# mainboard.net
KiCad netlist of a schematic drawn in EAGLE
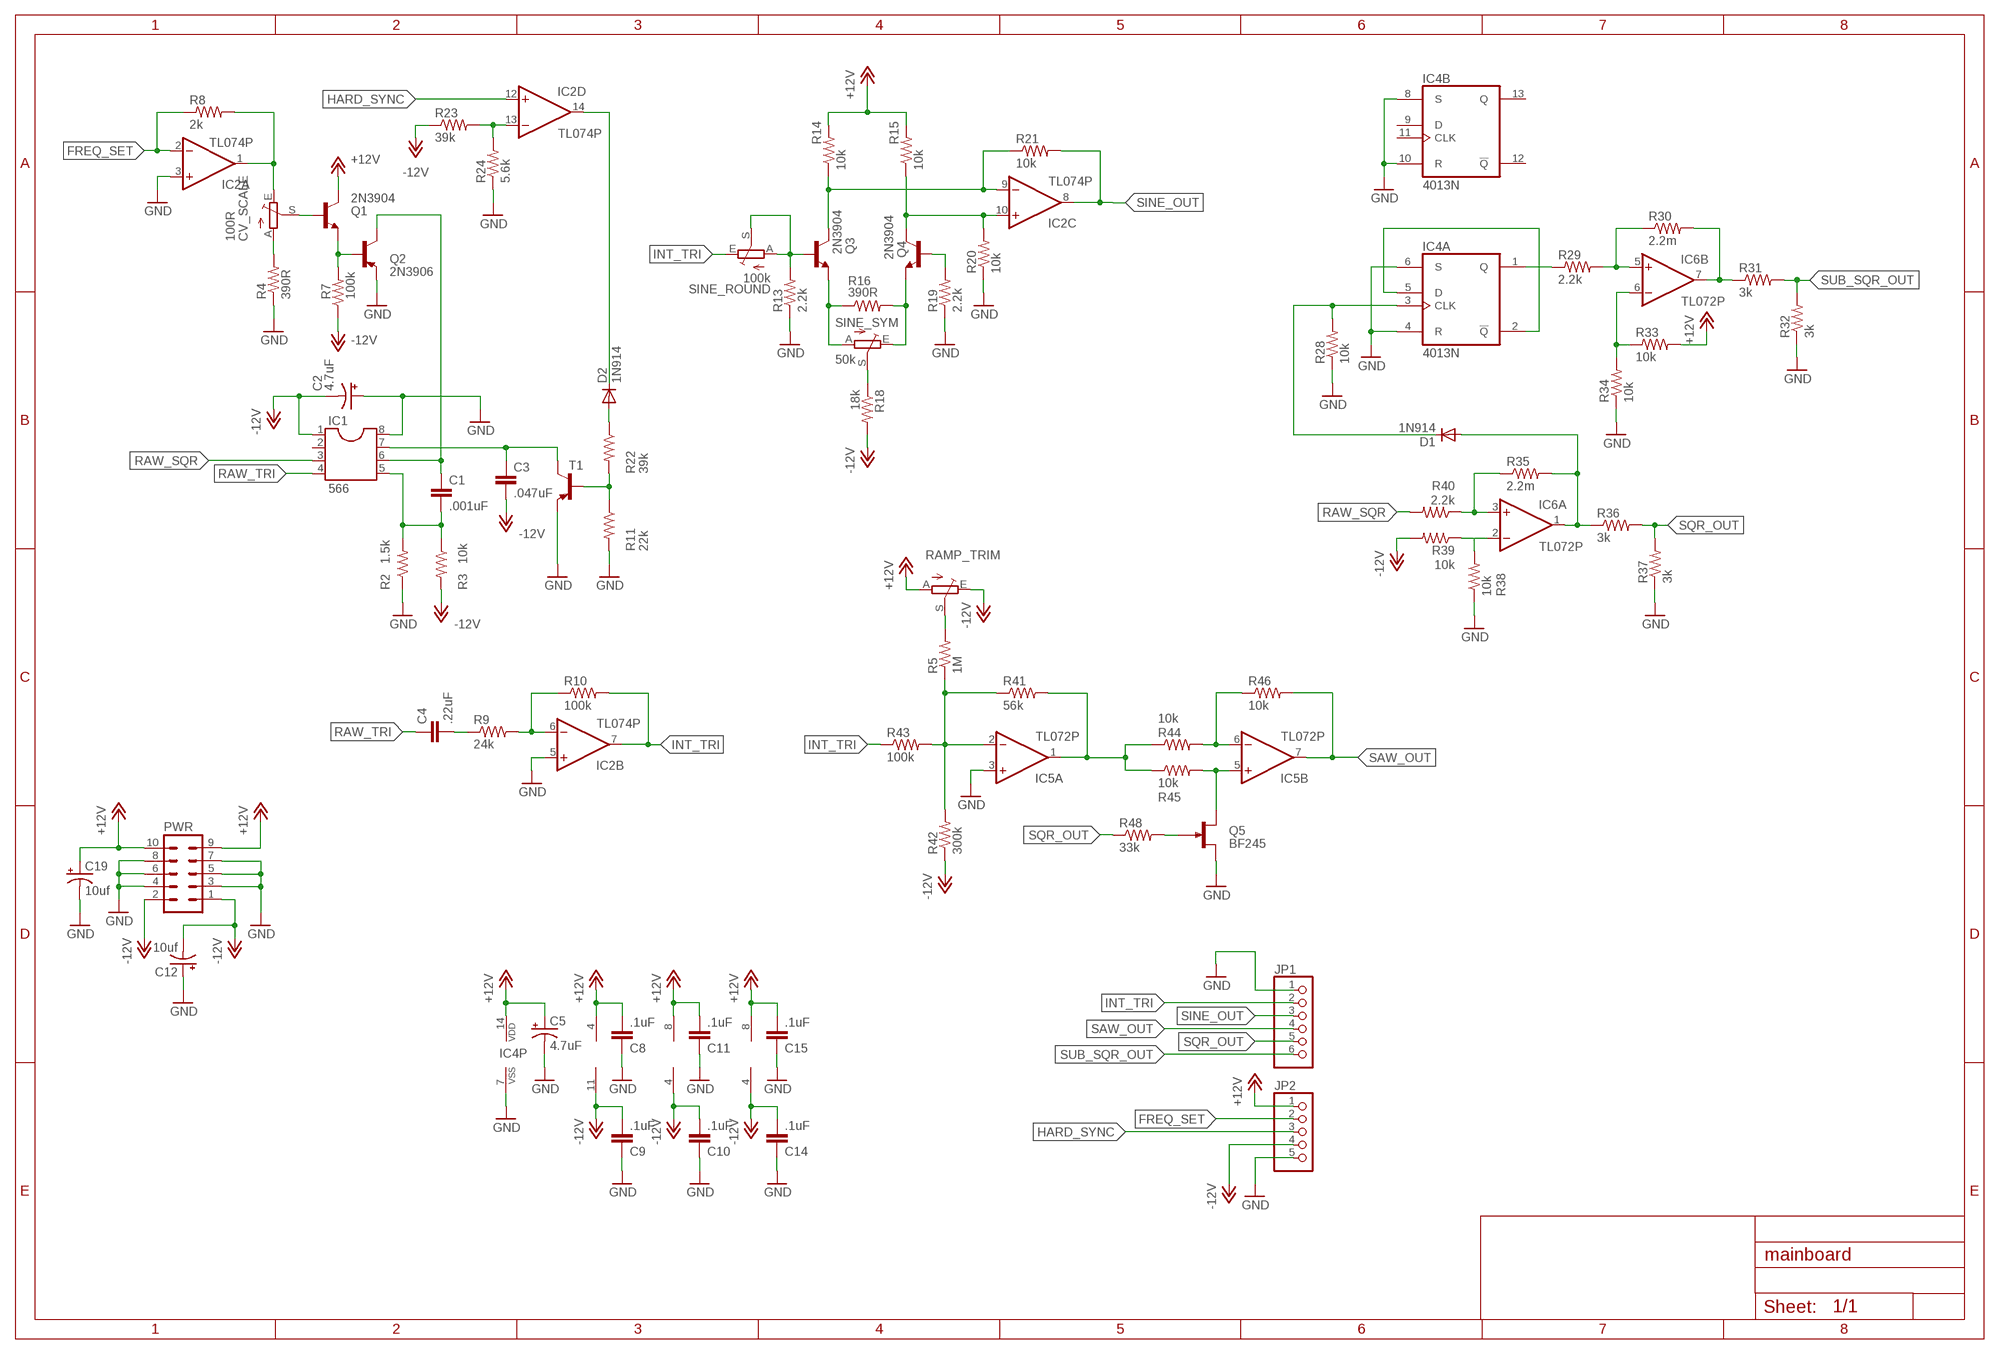
[diagram p0: schematic, sheet 1]

(export (version "E")
  (design (tool "Eeschema 10.0.6"))
  (components
    (comp (ref "C1")
      (value ".001uF")
      (footprint "eagle-import:C050-024X044")
      (libsource (lib "eagle-import") (part "C-EU050-024X044"))
    )
    (comp (ref "C2")
      (value "4.7uF")
      (footprint "eagle-import:E2,5-6")
      (libsource (lib "eagle-import") (part "CPOL-USE2.5-6"))
    )
    (comp (ref "C3")
      (value ".047uF")
      (footprint "eagle-import:C050-024X044")
      (libsource (lib "eagle-import") (part "C-EU050-024X044"))
    )
    (comp (ref "C4")
      (value ".22uF")
      (footprint "eagle-import:C050-024X044")
      (libsource (lib "eagle-import") (part "C-EU050-024X044"))
    )
    (comp (ref "C5")
      (value "4.7uF")
      (footprint "eagle-import:E2,5-5")
      (libsource (lib "eagle-import") (part "CPOL-USE2.5-5"))
    )
    (comp (ref "C8")
      (value ".1uF")
      (footprint "eagle-import:C050-024X044")
      (libsource (lib "eagle-import") (part "C-EU050-024X044"))
    )
    (comp (ref "C9")
      (value ".1uF")
      (footprint "eagle-import:C050-024X044")
      (libsource (lib "eagle-import") (part "C-EU050-024X044"))
    )
    (comp (ref "C10")
      (value ".1uF")
      (footprint "eagle-import:C050-024X044")
      (libsource (lib "eagle-import") (part "C-EU050-024X044"))
    )
    (comp (ref "C11")
      (value ".1uF")
      (footprint "eagle-import:C050-024X044")
      (libsource (lib "eagle-import") (part "C-EU050-024X044"))
    )
    (comp (ref "C12")
      (value "10uf")
      (footprint "eagle-import:E2,5-5")
      (libsource (lib "eagle-import") (part "CPOL-USE2.5-5"))
    )
    (comp (ref "C14")
      (value ".1uF")
      (footprint "eagle-import:C050-024X044")
      (libsource (lib "eagle-import") (part "C-EU050-024X044"))
    )
    (comp (ref "C15")
      (value ".1uF")
      (footprint "eagle-import:C050-024X044")
      (libsource (lib "eagle-import") (part "C-EU050-024X044"))
    )
    (comp (ref "C19")
      (value "10uf")
      (footprint "eagle-import:E2,5-5")
      (libsource (lib "eagle-import") (part "CPOL-USE2.5-5"))
    )
    (comp (ref "CV_SCALE")
      (value "100R")
      (footprint "eagle-import:RJ9W")
      (libsource (lib "eagle-import") (part "TRIM_EU-RJ9W"))
    )
    (comp (ref "D1")
      (value "1N914")
      (footprint "eagle-import:DO35-7")
      (libsource (lib "eagle-import") (part "1N4148DO35-7"))
    )
    (comp (ref "D2")
      (value "1N914")
      (footprint "eagle-import:DO35-7")
      (libsource (lib "eagle-import") (part "1N4148DO35-7"))
    )
    (comp (ref "IC1")
      (value "566")
      (footprint "eagle-import:DIL08")
      (libsource (lib "eagle-import") (part "DIL8"))
    )
    (comp (ref "IC2")
      (value "TL074P")
      (footprint "eagle-import:DIL14")
      (libsource (lib "eagle-import") (part "TL074P"))
    )
    (comp (ref "IC4")
      (value "4013N")
      (footprint "eagle-import:DIL14")
      (libsource (lib "eagle-import") (part "4013N"))
    )
    (comp (ref "IC5")
      (value "TL072P")
      (footprint "eagle-import:DIL08")
      (libsource (lib "eagle-import") (part "TL072P"))
    )
    (comp (ref "IC6")
      (value "TL072P")
      (footprint "eagle-import:DIL08")
      (libsource (lib "eagle-import") (part "TL072P"))
    )
    (comp (ref "JP1")
      (value "PINHD-1X6")
      (footprint "eagle-import:1X06")
      (libsource (lib "eagle-import") (part "PINHD-1X6"))
    )
    (comp (ref "JP2")
      (value "PINHD-1X5")
      (footprint "eagle-import:1X05")
      (libsource (lib "eagle-import") (part "PINHD-1X5"))
    )
    (comp (ref "PWR")
      (value "ML10")
      (footprint "eagle-import:ML10")
      (libsource (lib "eagle-import") (part "ML10"))
    )
    (comp (ref "Q1")
      (value "2N3904")
      (footprint "eagle-import:TO92")
      (libsource (lib "eagle-import") (part "2N3904"))
    )
    (comp (ref "Q2")
      (value "2N3906")
      (footprint "eagle-import:TO92")
      (libsource (lib "eagle-import") (part "2N3906"))
    )
    (comp (ref "Q3")
      (value "2N3904")
      (footprint "eagle-import:TO92")
      (libsource (lib "eagle-import") (part "2N3904"))
    )
    (comp (ref "Q4")
      (value "2N3904")
      (footprint "eagle-import:TO92")
      (libsource (lib "eagle-import") (part "2N3904"))
    )
    (comp (ref "Q5")
      (value "BF245")
      (footprint "eagle-import:SOT54C")
      (libsource (lib "eagle-import") (part "BF245"))
    )
    (comp (ref "R2")
      (value "1.5k")
      (footprint "eagle-import:0204_7")
      (libsource (lib "eagle-import") (part "R-US_0204/7"))
    )
    (comp (ref "R3")
      (value "10k")
      (footprint "eagle-import:0204_7")
      (libsource (lib "eagle-import") (part "R-US_0204/7"))
    )
    (comp (ref "R4")
      (value "390R")
      (footprint "eagle-import:0204_7")
      (libsource (lib "eagle-import") (part "R-US_0204/7"))
    )
    (comp (ref "R5")
      (value "1M")
      (footprint "eagle-import:0204_7")
      (libsource (lib "eagle-import") (part "R-US_0204/7"))
    )
    (comp (ref "R7")
      (value "100k")
      (footprint "eagle-import:0204_7")
      (libsource (lib "eagle-import") (part "R-US_0204/7"))
    )
    (comp (ref "R8")
      (value "2k")
      (footprint "eagle-import:0204_7")
      (libsource (lib "eagle-import") (part "R-US_0204/7"))
    )
    (comp (ref "R9")
      (value "24k")
      (footprint "eagle-import:0204_7")
      (libsource (lib "eagle-import") (part "R-US_0204/7"))
    )
    (comp (ref "R10")
      (value "100k")
      (footprint "eagle-import:0204_7")
      (libsource (lib "eagle-import") (part "R-US_0204/7"))
    )
    (comp (ref "R11")
      (value "22k")
      (footprint "eagle-import:0204_7")
      (libsource (lib "eagle-import") (part "R-US_0204/7"))
    )
    (comp (ref "R13")
      (value "2.2k")
      (footprint "eagle-import:0204_7")
      (libsource (lib "eagle-import") (part "R-US_0204/7"))
    )
    (comp (ref "R14")
      (value "10k")
      (footprint "eagle-import:0204_7")
      (libsource (lib "eagle-import") (part "R-US_0204/7"))
    )
    (comp (ref "R15")
      (value "10k")
      (footprint "eagle-import:0204_7")
      (libsource (lib "eagle-import") (part "R-US_0204/7"))
    )
    (comp (ref "R16")
      (value "390R")
      (footprint "eagle-import:0204_7")
      (libsource (lib "eagle-import") (part "R-US_0204/7"))
    )
    (comp (ref "R18")
      (value "18k")
      (footprint "eagle-import:0204_7")
      (libsource (lib "eagle-import") (part "R-US_0204/7"))
    )
    (comp (ref "R19")
      (value "2.2k")
      (footprint "eagle-import:0204_7")
      (libsource (lib "eagle-import") (part "R-US_0204/7"))
    )
    (comp (ref "R20")
      (value "10k")
      (footprint "eagle-import:0204_7")
      (libsource (lib "eagle-import") (part "R-US_0204/7"))
    )
    (comp (ref "R21")
      (value "10k")
      (footprint "eagle-import:0204_7")
      (libsource (lib "eagle-import") (part "R-US_0204/7"))
    )
    (comp (ref "R22")
      (value "39k")
      (footprint "eagle-import:0204_7")
      (libsource (lib "eagle-import") (part "R-US_0204/7"))
    )
    (comp (ref "R23")
      (value "39k")
      (footprint "eagle-import:0204_7")
      (libsource (lib "eagle-import") (part "R-US_0204/7"))
    )
    (comp (ref "R24")
      (value "5.6k")
      (footprint "eagle-import:0204_7")
      (libsource (lib "eagle-import") (part "R-US_0204/7"))
    )
    (comp (ref "R28")
      (value "10k")
      (footprint "eagle-import:0204_7")
      (libsource (lib "eagle-import") (part "R-US_0204/7"))
    )
    (comp (ref "R29")
      (value "2.2k")
      (footprint "eagle-import:0204_7")
      (libsource (lib "eagle-import") (part "R-US_0204/7"))
    )
    (comp (ref "R30")
      (value "2.2m")
      (footprint "eagle-import:0204_7")
      (libsource (lib "eagle-import") (part "R-US_0204/7"))
    )
    (comp (ref "R31")
      (value "3k")
      (footprint "eagle-import:0204_7")
      (libsource (lib "eagle-import") (part "R-US_0204/7"))
    )
    (comp (ref "R32")
      (value "3k")
      (footprint "eagle-import:0204_7")
      (libsource (lib "eagle-import") (part "R-US_0204/7"))
    )
    (comp (ref "R33")
      (value "10k")
      (footprint "eagle-import:0204_7")
      (libsource (lib "eagle-import") (part "R-US_0204/7"))
    )
    (comp (ref "R34")
      (value "10k")
      (footprint "eagle-import:0204_7")
      (libsource (lib "eagle-import") (part "R-US_0204/7"))
    )
    (comp (ref "R35")
      (value "2.2m")
      (footprint "eagle-import:0204_7")
      (libsource (lib "eagle-import") (part "R-US_0204/7"))
    )
    (comp (ref "R36")
      (value "3k")
      (footprint "eagle-import:0204_7")
      (libsource (lib "eagle-import") (part "R-US_0204/7"))
    )
    (comp (ref "R37")
      (value "3k")
      (footprint "eagle-import:0204_7")
      (libsource (lib "eagle-import") (part "R-US_0204/7"))
    )
    (comp (ref "R38")
      (value "10k")
      (footprint "eagle-import:0204_7")
      (libsource (lib "eagle-import") (part "R-US_0204/7"))
    )
    (comp (ref "R39")
      (value "10k")
      (footprint "eagle-import:0204_7")
      (libsource (lib "eagle-import") (part "R-US_0204/7"))
    )
    (comp (ref "R40")
      (value "2.2k")
      (footprint "eagle-import:0204_7")
      (libsource (lib "eagle-import") (part "R-US_0204/7"))
    )
    (comp (ref "R41")
      (value "56k")
      (footprint "eagle-import:0204_7")
      (libsource (lib "eagle-import") (part "R-US_0204/7"))
    )
    (comp (ref "R42")
      (value "300k")
      (footprint "eagle-import:0204_7")
      (libsource (lib "eagle-import") (part "R-US_0204/7"))
    )
    (comp (ref "R43")
      (value "100k")
      (footprint "eagle-import:0204_7")
      (libsource (lib "eagle-import") (part "R-US_0204/7"))
    )
    (comp (ref "R44")
      (value "10k")
      (footprint "eagle-import:0204_7")
      (libsource (lib "eagle-import") (part "R-US_0204/7"))
    )
    (comp (ref "R45")
      (value "10k")
      (footprint "eagle-import:0204_7")
      (libsource (lib "eagle-import") (part "R-US_0204/7"))
    )
    (comp (ref "R46")
      (value "10k")
      (footprint "eagle-import:0204_7")
      (libsource (lib "eagle-import") (part "R-US_0204/7"))
    )
    (comp (ref "R48")
      (value "33k")
      (footprint "eagle-import:0204_7")
      (libsource (lib "eagle-import") (part "R-US_0204/7"))
    )
    (comp (ref "RAMP_TRIM")
      (value "TRIM_EU-RJ9W")
      (footprint "eagle-import:RJ9W")
      (libsource (lib "eagle-import") (part "TRIM_EU-RJ9W"))
    )
    (comp (ref "SINE_ROUND")
      (value "100k")
      (footprint "eagle-import:RJ9W")
      (libsource (lib "eagle-import") (part "TRIM_EU-RJ9W"))
    )
    (comp (ref "SINE_SYM")
      (value "50k")
      (footprint "eagle-import:RJ9W")
      (libsource (lib "eagle-import") (part "TRIM_EU-RJ9W"))
    )
    (comp (ref "T1")
      (value "2N3906-PNP-TO92-EBC")
      (footprint "eagle-import:TO92-EBC")
      (libsource (lib "eagle-import") (part "-PNP-TO92-EBC2N3906"))
    )
  )
  (nets
    (net (code "1") (name "+12V") (class "Default")
      (node (ref "C11") (pin "2") (pinfunction "2_2") (pintype "passive"))
      (node (ref "C15") (pin "2") (pinfunction "2_2") (pintype "passive"))
      (node (ref "C19") (pin "+") (pinfunction "+_+") (pintype "passive"))
      (node (ref "C5") (pin "+") (pinfunction "+_+") (pintype "passive"))
      (node (ref "C8") (pin "2") (pinfunction "2_2") (pintype "passive"))
      (node (ref "IC2") (pin "4") (pinfunction "V+_4") (pintype "power_in"))
      (node (ref "IC4") (pin "14") (pinfunction "VDD_14") (pintype "power_in"))
      (node (ref "IC5") (pin "8") (pinfunction "V+_8") (pintype "power_in"))
      (node (ref "IC6") (pin "8") (pinfunction "V+_8") (pintype "power_in"))
      (node (ref "JP2") (pin "1") (pinfunction "1_1") (pintype "passive"))
      (node (ref "PWR") (pin "10") (pinfunction "10_10") (pintype "passive"))
      (node (ref "PWR") (pin "9") (pinfunction "9_9") (pintype "passive"))
      (node (ref "Q1") (pin "1") (pinfunction "C_1") (pintype "passive"))
      (node (ref "R14") (pin "2") (pinfunction "2_2") (pintype "passive"))
      (node (ref "R15") (pin "2") (pinfunction "2_2") (pintype "passive"))
      (node (ref "R33") (pin "2") (pinfunction "2_2") (pintype "passive"))
      (node (ref "RAMP_TRIM") (pin "A") (pinfunction "A_A") (pintype "passive"))
    )
    (net (code "2") (name "-12V") (class "Default")
      (node (ref "C10") (pin "2") (pinfunction "2_2") (pintype "passive"))
      (node (ref "C12") (pin "-") (pinfunction "-_-") (pintype "passive"))
      (node (ref "C14") (pin "2") (pinfunction "2_2") (pintype "passive"))
      (node (ref "C2") (pin "-") (pinfunction "-_-") (pintype "passive"))
      (node (ref "C3") (pin "2") (pinfunction "2_2") (pintype "passive"))
      (node (ref "C9") (pin "2") (pinfunction "2_2") (pintype "passive"))
      (node (ref "IC1") (pin "1") (pinfunction "1_1") (pintype "passive"))
      (node (ref "IC2") (pin "11") (pinfunction "V-_11") (pintype "power_in"))
      (node (ref "IC5") (pin "4") (pinfunction "V-_4") (pintype "power_in"))
      (node (ref "IC6") (pin "4") (pinfunction "V-_4") (pintype "power_in"))
      (node (ref "JP2") (pin "4") (pinfunction "4_4") (pintype "passive"))
      (node (ref "PWR") (pin "1") (pinfunction "1_1") (pintype "passive"))
      (node (ref "PWR") (pin "2") (pinfunction "2_2") (pintype "passive"))
      (node (ref "R18") (pin "2") (pinfunction "2_2") (pintype "passive"))
      (node (ref "R23") (pin "1") (pinfunction "1_1") (pintype "passive"))
      (node (ref "R3") (pin "2") (pinfunction "2_2") (pintype "passive"))
      (node (ref "R39") (pin "2") (pinfunction "2_2") (pintype "passive"))
      (node (ref "R42") (pin "1") (pinfunction "1_1") (pintype "passive"))
      (node (ref "R7") (pin "1") (pinfunction "1_1") (pintype "passive"))
      (node (ref "RAMP_TRIM") (pin "E") (pinfunction "E_E") (pintype "passive"))
    )
    (net (code "3") (name "FREQ_SET") (class "Default")
      (node (ref "IC2") (pin "2") (pinfunction "-IN_2") (pintype "input"))
      (node (ref "JP2") (pin "2") (pinfunction "2_2") (pintype "passive"))
      (node (ref "R8") (pin "1") (pinfunction "1_1") (pintype "passive"))
    )
    (net (code "4") (name "GND") (class "Default")
      (node (ref "C10") (pin "1") (pinfunction "1_1") (pintype "passive"))
      (node (ref "C11") (pin "1") (pinfunction "1_1") (pintype "passive"))
      (node (ref "C12") (pin "+") (pinfunction "+_+") (pintype "passive"))
      (node (ref "C14") (pin "1") (pinfunction "1_1") (pintype "passive"))
      (node (ref "C15") (pin "1") (pinfunction "1_1") (pintype "passive"))
      (node (ref "C19") (pin "-") (pinfunction "-_-") (pintype "passive"))
      (node (ref "C2") (pin "+") (pinfunction "+_+") (pintype "passive"))
      (node (ref "C5") (pin "-") (pinfunction "-_-") (pintype "passive"))
      (node (ref "C8") (pin "1") (pinfunction "1_1") (pintype "passive"))
      (node (ref "C9") (pin "1") (pinfunction "1_1") (pintype "passive"))
      (node (ref "IC1") (pin "8") (pinfunction "8_8") (pintype "passive"))
      (node (ref "IC2") (pin "3") (pinfunction "+IN_3") (pintype "input"))
      (node (ref "IC2") (pin "5") (pinfunction "+IN_5") (pintype "input"))
      (node (ref "IC4") (pin "10") (pinfunction "R_10") (pintype "input"))
      (node (ref "IC4") (pin "4") (pinfunction "R_4") (pintype "input"))
      (node (ref "IC4") (pin "6") (pinfunction "S_6") (pintype "input"))
      (node (ref "IC4") (pin "7") (pinfunction "VSS_7") (pintype "power_in"))
      (node (ref "IC4") (pin "8") (pinfunction "S_8") (pintype "input"))
      (node (ref "IC5") (pin "3") (pinfunction "+IN_3") (pintype "input"))
      (node (ref "JP1") (pin "1") (pinfunction "1_1") (pintype "passive"))
      (node (ref "JP2") (pin "5") (pinfunction "5_5") (pintype "passive"))
      (node (ref "PWR") (pin "3") (pinfunction "3_3") (pintype "passive"))
      (node (ref "PWR") (pin "4") (pinfunction "4_4") (pintype "passive"))
      (node (ref "PWR") (pin "5") (pinfunction "5_5") (pintype "passive"))
      (node (ref "PWR") (pin "6") (pinfunction "6_6") (pintype "passive"))
      (node (ref "PWR") (pin "7") (pinfunction "7_7") (pintype "passive"))
      (node (ref "PWR") (pin "8") (pinfunction "8_8") (pintype "passive"))
      (node (ref "Q2") (pin "3") (pinfunction "E_3") (pintype "passive"))
      (node (ref "Q5") (pin "S") (pinfunction "S_S") (pintype "passive"))
      (node (ref "R11") (pin "2") (pinfunction "2_2") (pintype "passive"))
      (node (ref "R13") (pin "1") (pinfunction "1_1") (pintype "passive"))
      (node (ref "R19") (pin "1") (pinfunction "1_1") (pintype "passive"))
      (node (ref "R2") (pin "1") (pinfunction "1_1") (pintype "passive"))
      (node (ref "R20") (pin "1") (pinfunction "1_1") (pintype "passive"))
      (node (ref "R24") (pin "1") (pinfunction "1_1") (pintype "passive"))
      (node (ref "R28") (pin "1") (pinfunction "1_1") (pintype "passive"))
      (node (ref "R32") (pin "1") (pinfunction "1_1") (pintype "passive"))
      (node (ref "R34") (pin "1") (pinfunction "1_1") (pintype "passive"))
      (node (ref "R37") (pin "1") (pinfunction "1_1") (pintype "passive"))
      (node (ref "R38") (pin "1") (pinfunction "1_1") (pintype "passive"))
      (node (ref "R4") (pin "1") (pinfunction "1_1") (pintype "passive"))
      (node (ref "T1") (pin "E") (pinfunction "E_E") (pintype "passive"))
    )
    (net (code "5") (name "HARD_SYNC") (class "Default")
      (node (ref "IC2") (pin "12") (pinfunction "+IN_12") (pintype "input"))
      (node (ref "JP2") (pin "3") (pinfunction "3_3") (pintype "passive"))
    )
    (net (code "6") (name "INT_TRI") (class "Default")
      (node (ref "IC2") (pin "7") (pinfunction "OUT_7") (pintype "output"))
      (node (ref "JP1") (pin "2") (pinfunction "2_2") (pintype "passive"))
      (node (ref "R10") (pin "2") (pinfunction "2_2") (pintype "passive"))
      (node (ref "R43") (pin "1") (pinfunction "1_1") (pintype "passive"))
      (node (ref "SINE_ROUND") (pin "E") (pinfunction "E_E") (pintype "passive"))
    )
    (net (code "7") (name "Net-(C1-Pad2)") (class "Default")
      (node (ref "C1") (pin "2") (pinfunction "2_2") (pintype "passive"))
      (node (ref "IC1") (pin "5") (pinfunction "5_5") (pintype "passive"))
      (node (ref "R2") (pin "2") (pinfunction "2_2") (pintype "passive"))
      (node (ref "R3") (pin "1") (pinfunction "1_1") (pintype "passive"))
    )
    (net (code "8") (name "Net-(C3-Pad1)") (class "Default")
      (node (ref "C3") (pin "1") (pinfunction "1_1") (pintype "passive"))
      (node (ref "IC1") (pin "7") (pinfunction "7_7") (pintype "passive"))
      (node (ref "T1") (pin "C") (pinfunction "C_C") (pintype "passive"))
    )
    (net (code "9") (name "Net-(C4-Pad2)") (class "Default")
      (node (ref "C4") (pin "2") (pinfunction "2_2") (pintype "passive"))
      (node (ref "R9") (pin "1") (pinfunction "1_1") (pintype "passive"))
    )
    (net (code "10") (name "Net-(CV_SCALE-PadA)") (class "Default")
      (node (ref "CV_SCALE") (pin "A") (pinfunction "A_A") (pintype "passive"))
      (node (ref "R4") (pin "2") (pinfunction "2_2") (pintype "passive"))
    )
    (net (code "11") (name "Net-(D2-PadA)") (class "Default")
      (node (ref "D2") (pin "A") (pinfunction "A_A") (pintype "passive"))
      (node (ref "R22") (pin "1") (pinfunction "1_1") (pintype "passive"))
    )
    (net (code "12") (name "Net-(IC2A-OUT)") (class "Default")
      (node (ref "CV_SCALE") (pin "E") (pinfunction "E_E") (pintype "passive"))
      (node (ref "IC2") (pin "1") (pinfunction "OUT_1") (pintype "output"))
      (node (ref "R8") (pin "2") (pinfunction "2_2") (pintype "passive"))
    )
    (net (code "13") (name "Net-(IC2B--IN)") (class "Default")
      (node (ref "IC2") (pin "6") (pinfunction "-IN_6") (pintype "input"))
      (node (ref "R10") (pin "1") (pinfunction "1_1") (pintype "passive"))
      (node (ref "R9") (pin "2") (pinfunction "2_2") (pintype "passive"))
    )
    (net (code "14") (name "Net-(IC2C-+IN)") (class "Default")
      (node (ref "IC2") (pin "10") (pinfunction "+IN_10") (pintype "input"))
      (node (ref "Q4") (pin "1") (pinfunction "C_1") (pintype "passive"))
      (node (ref "R15") (pin "1") (pinfunction "1_1") (pintype "passive"))
      (node (ref "R20") (pin "2") (pinfunction "2_2") (pintype "passive"))
    )
    (net (code "15") (name "Net-(IC2C--IN)") (class "Default")
      (node (ref "IC2") (pin "9") (pinfunction "-IN_9") (pintype "input"))
      (node (ref "Q3") (pin "1") (pinfunction "C_1") (pintype "passive"))
      (node (ref "R14") (pin "1") (pinfunction "1_1") (pintype "passive"))
      (node (ref "R21") (pin "1") (pinfunction "1_1") (pintype "passive"))
    )
    (net (code "16") (name "Net-(IC2D--IN)") (class "Default")
      (node (ref "IC2") (pin "13") (pinfunction "-IN_13") (pintype "input"))
      (node (ref "R23") (pin "2") (pinfunction "2_2") (pintype "passive"))
      (node (ref "R24") (pin "2") (pinfunction "2_2") (pintype "passive"))
    )
    (net (code "17") (name "Net-(IC2D-OUT)") (class "Default")
      (node (ref "D2") (pin "C") (pinfunction "C_C") (pintype "passive"))
      (node (ref "IC2") (pin "14") (pinfunction "OUT_14") (pintype "output"))
    )
    (net (code "18") (name "Net-(IC4A-CLK)") (class "Default")
      (node (ref "D1") (pin "C") (pinfunction "C_C") (pintype "passive"))
      (node (ref "IC4") (pin "3") (pinfunction "CLK_3") (pintype "input"))
      (node (ref "R28") (pin "2") (pinfunction "2_2") (pintype "passive"))
    )
    (net (code "19") (name "Net-(IC4A-D)") (class "Default")
      (node (ref "IC4") (pin "2") (pinfunction "~{Q}_2") (pintype "output"))
      (node (ref "IC4") (pin "5") (pinfunction "D_5") (pintype "input"))
    )
    (net (code "20") (name "Net-(IC4A-Q)") (class "Default")
      (node (ref "IC4") (pin "1") (pinfunction "Q_1") (pintype "output"))
      (node (ref "R29") (pin "1") (pinfunction "1_1") (pintype "passive"))
    )
    (net (code "21") (name "Net-(IC5A--IN)") (class "Default")
      (node (ref "IC5") (pin "2") (pinfunction "-IN_2") (pintype "input"))
      (node (ref "R41") (pin "1") (pinfunction "1_1") (pintype "passive"))
      (node (ref "R42") (pin "2") (pinfunction "2_2") (pintype "passive"))
      (node (ref "R43") (pin "2") (pinfunction "2_2") (pintype "passive"))
      (node (ref "R5") (pin "1") (pinfunction "1_1") (pintype "passive"))
    )
    (net (code "22") (name "Net-(IC5A-OUT)") (class "Default")
      (node (ref "IC5") (pin "1") (pinfunction "OUT_1") (pintype "output"))
      (node (ref "R41") (pin "2") (pinfunction "2_2") (pintype "passive"))
      (node (ref "R44") (pin "1") (pinfunction "1_1") (pintype "passive"))
      (node (ref "R45") (pin "1") (pinfunction "1_1") (pintype "passive"))
    )
    (net (code "23") (name "Net-(IC5B-+IN)") (class "Default")
      (node (ref "IC5") (pin "5") (pinfunction "+IN_5") (pintype "input"))
      (node (ref "Q5") (pin "D") (pinfunction "D_D") (pintype "passive"))
      (node (ref "R45") (pin "2") (pinfunction "2_2") (pintype "passive"))
    )
    (net (code "24") (name "Net-(IC5B--IN)") (class "Default")
      (node (ref "IC5") (pin "6") (pinfunction "-IN_6") (pintype "input"))
      (node (ref "R44") (pin "2") (pinfunction "2_2") (pintype "passive"))
      (node (ref "R46") (pin "1") (pinfunction "1_1") (pintype "passive"))
    )
    (net (code "25") (name "Net-(IC6A-+IN)") (class "Default")
      (node (ref "IC6") (pin "3") (pinfunction "+IN_3") (pintype "input"))
      (node (ref "R35") (pin "1") (pinfunction "1_1") (pintype "passive"))
      (node (ref "R40") (pin "1") (pinfunction "1_1") (pintype "passive"))
    )
    (net (code "26") (name "Net-(IC6A--IN)") (class "Default")
      (node (ref "IC6") (pin "2") (pinfunction "-IN_2") (pintype "input"))
      (node (ref "R38") (pin "2") (pinfunction "2_2") (pintype "passive"))
      (node (ref "R39") (pin "1") (pinfunction "1_1") (pintype "passive"))
    )
    (net (code "27") (name "Net-(IC6A-OUT)") (class "Default")
      (node (ref "D1") (pin "A") (pinfunction "A_A") (pintype "passive"))
      (node (ref "IC6") (pin "1") (pinfunction "OUT_1") (pintype "output"))
      (node (ref "R35") (pin "2") (pinfunction "2_2") (pintype "passive"))
      (node (ref "R36") (pin "1") (pinfunction "1_1") (pintype "passive"))
    )
    (net (code "28") (name "Net-(IC6B-+IN)") (class "Default")
      (node (ref "IC6") (pin "5") (pinfunction "+IN_5") (pintype "input"))
      (node (ref "R29") (pin "2") (pinfunction "2_2") (pintype "passive"))
      (node (ref "R30") (pin "1") (pinfunction "1_1") (pintype "passive"))
    )
    (net (code "29") (name "Net-(IC6B--IN)") (class "Default")
      (node (ref "IC6") (pin "6") (pinfunction "-IN_6") (pintype "input"))
      (node (ref "R33") (pin "1") (pinfunction "1_1") (pintype "passive"))
      (node (ref "R34") (pin "2") (pinfunction "2_2") (pintype "passive"))
    )
    (net (code "30") (name "Net-(IC6B-OUT)") (class "Default")
      (node (ref "IC6") (pin "7") (pinfunction "OUT_7") (pintype "output"))
      (node (ref "R30") (pin "2") (pinfunction "2_2") (pintype "passive"))
      (node (ref "R31") (pin "1") (pinfunction "1_1") (pintype "passive"))
    )
    (net (code "31") (name "Net-(Q1-B)") (class "Default")
      (node (ref "CV_SCALE") (pin "S") (pinfunction "S_S") (pintype "passive"))
      (node (ref "Q1") (pin "2") (pinfunction "B_2") (pintype "passive"))
    )
    (net (code "32") (name "Net-(Q1-E)") (class "Default")
      (node (ref "Q1") (pin "3") (pinfunction "E_3") (pintype "passive"))
      (node (ref "Q2") (pin "2") (pinfunction "B_2") (pintype "passive"))
      (node (ref "R7") (pin "2") (pinfunction "2_2") (pintype "passive"))
    )
    (net (code "33") (name "Net-(Q2-C)") (class "Default")
      (node (ref "C1") (pin "1") (pinfunction "1_1") (pintype "passive"))
      (node (ref "IC1") (pin "6") (pinfunction "6_6") (pintype "passive"))
      (node (ref "Q2") (pin "1") (pinfunction "C_1") (pintype "passive"))
    )
    (net (code "34") (name "Net-(Q3-B)") (class "Default")
      (node (ref "Q3") (pin "2") (pinfunction "B_2") (pintype "passive"))
      (node (ref "R13") (pin "2") (pinfunction "2_2") (pintype "passive"))
      (node (ref "SINE_ROUND") (pin "A") (pinfunction "A_A") (pintype "passive"))
      (node (ref "SINE_ROUND") (pin "S") (pinfunction "S_S") (pintype "passive"))
    )
    (net (code "35") (name "Net-(Q3-E)") (class "Default")
      (node (ref "Q3") (pin "3") (pinfunction "E_3") (pintype "passive"))
      (node (ref "R16") (pin "1") (pinfunction "1_1") (pintype "passive"))
      (node (ref "SINE_SYM") (pin "A") (pinfunction "A_A") (pintype "passive"))
    )
    (net (code "36") (name "Net-(Q4-B)") (class "Default")
      (node (ref "Q4") (pin "2") (pinfunction "B_2") (pintype "passive"))
      (node (ref "R19") (pin "2") (pinfunction "2_2") (pintype "passive"))
    )
    (net (code "37") (name "Net-(Q4-E)") (class "Default")
      (node (ref "Q4") (pin "3") (pinfunction "E_3") (pintype "passive"))
      (node (ref "R16") (pin "2") (pinfunction "2_2") (pintype "passive"))
      (node (ref "SINE_SYM") (pin "E") (pinfunction "E_E") (pintype "passive"))
    )
    (net (code "38") (name "Net-(Q5-PadG)") (class "Default")
      (node (ref "Q5") (pin "G") (pinfunction "G_G") (pintype "passive"))
      (node (ref "R48") (pin "2") (pinfunction "2_2") (pintype "passive"))
    )
    (net (code "39") (name "Net-(R5-Pad2)") (class "Default")
      (node (ref "R5") (pin "2") (pinfunction "2_2") (pintype "passive"))
      (node (ref "RAMP_TRIM") (pin "S") (pinfunction "S_S") (pintype "passive"))
    )
    (net (code "40") (name "Net-(R11-Pad1)") (class "Default")
      (node (ref "R11") (pin "1") (pinfunction "1_1") (pintype "passive"))
      (node (ref "R22") (pin "2") (pinfunction "2_2") (pintype "passive"))
      (node (ref "T1") (pin "B") (pinfunction "B_B") (pintype "passive"))
    )
    (net (code "41") (name "Net-(R18-Pad1)") (class "Default")
      (node (ref "R18") (pin "1") (pinfunction "1_1") (pintype "passive"))
      (node (ref "SINE_SYM") (pin "S") (pinfunction "S_S") (pintype "passive"))
    )
    (net (code "42") (name "RAW_SQR") (class "Default")
      (node (ref "IC1") (pin "3") (pinfunction "3_3") (pintype "passive"))
      (node (ref "R40") (pin "2") (pinfunction "2_2") (pintype "passive"))
    )
    (net (code "43") (name "RAW_TRI") (class "Default")
      (node (ref "C4") (pin "1") (pinfunction "1_1") (pintype "passive"))
      (node (ref "IC1") (pin "4") (pinfunction "4_4") (pintype "passive"))
    )
    (net (code "44") (name "SAW_OUT") (class "Default")
      (node (ref "IC5") (pin "7") (pinfunction "OUT_7") (pintype "output"))
      (node (ref "JP1") (pin "4") (pinfunction "4_4") (pintype "passive"))
      (node (ref "R46") (pin "2") (pinfunction "2_2") (pintype "passive"))
    )
    (net (code "45") (name "SINE_OUT") (class "Default")
      (node (ref "IC2") (pin "8") (pinfunction "OUT_8") (pintype "output"))
      (node (ref "JP1") (pin "3") (pinfunction "3_3") (pintype "passive"))
      (node (ref "R21") (pin "2") (pinfunction "2_2") (pintype "passive"))
    )
    (net (code "46") (name "SQR_OUT") (class "Default")
      (node (ref "JP1") (pin "5") (pinfunction "5_5") (pintype "passive"))
      (node (ref "R36") (pin "2") (pinfunction "2_2") (pintype "passive"))
      (node (ref "R37") (pin "2") (pinfunction "2_2") (pintype "passive"))
      (node (ref "R48") (pin "1") (pinfunction "1_1") (pintype "passive"))
    )
    (net (code "47") (name "SUB_SQR_OUT") (class "Default")
      (node (ref "JP1") (pin "6") (pinfunction "6_6") (pintype "passive"))
      (node (ref "R31") (pin "2") (pinfunction "2_2") (pintype "passive"))
      (node (ref "R32") (pin "2") (pinfunction "2_2") (pintype "passive"))
    )
    (net (code "48") (name "unconnected-(IC1-Pad2)") (class "Default")
      (node (ref "IC1") (pin "2") (pinfunction "2_2") (pintype "passive"))
    )
    (net (code "49") (name "unconnected-(IC4B-CLK-Pad11)") (class "Default")
      (node (ref "IC4") (pin "11") (pinfunction "CLK_11") (pintype "input"))
    )
    (net (code "50") (name "unconnected-(IC4B-D-Pad9)") (class "Default")
      (node (ref "IC4") (pin "9") (pinfunction "D_9") (pintype "input"))
    )
    (net (code "51") (name "unconnected-(IC4B-Q-Pad13)") (class "Default")
      (node (ref "IC4") (pin "13") (pinfunction "Q_13") (pintype "output"))
    )
    (net (code "52") (name "unconnected-(IC4B-~{Q}-Pad12)") (class "Default")
      (node (ref "IC4") (pin "12") (pinfunction "~{Q}_12") (pintype "output"))
    )
  )
)
